# Virulent_HW.net
KiCad netlist of a schematic drawn in EAGLE
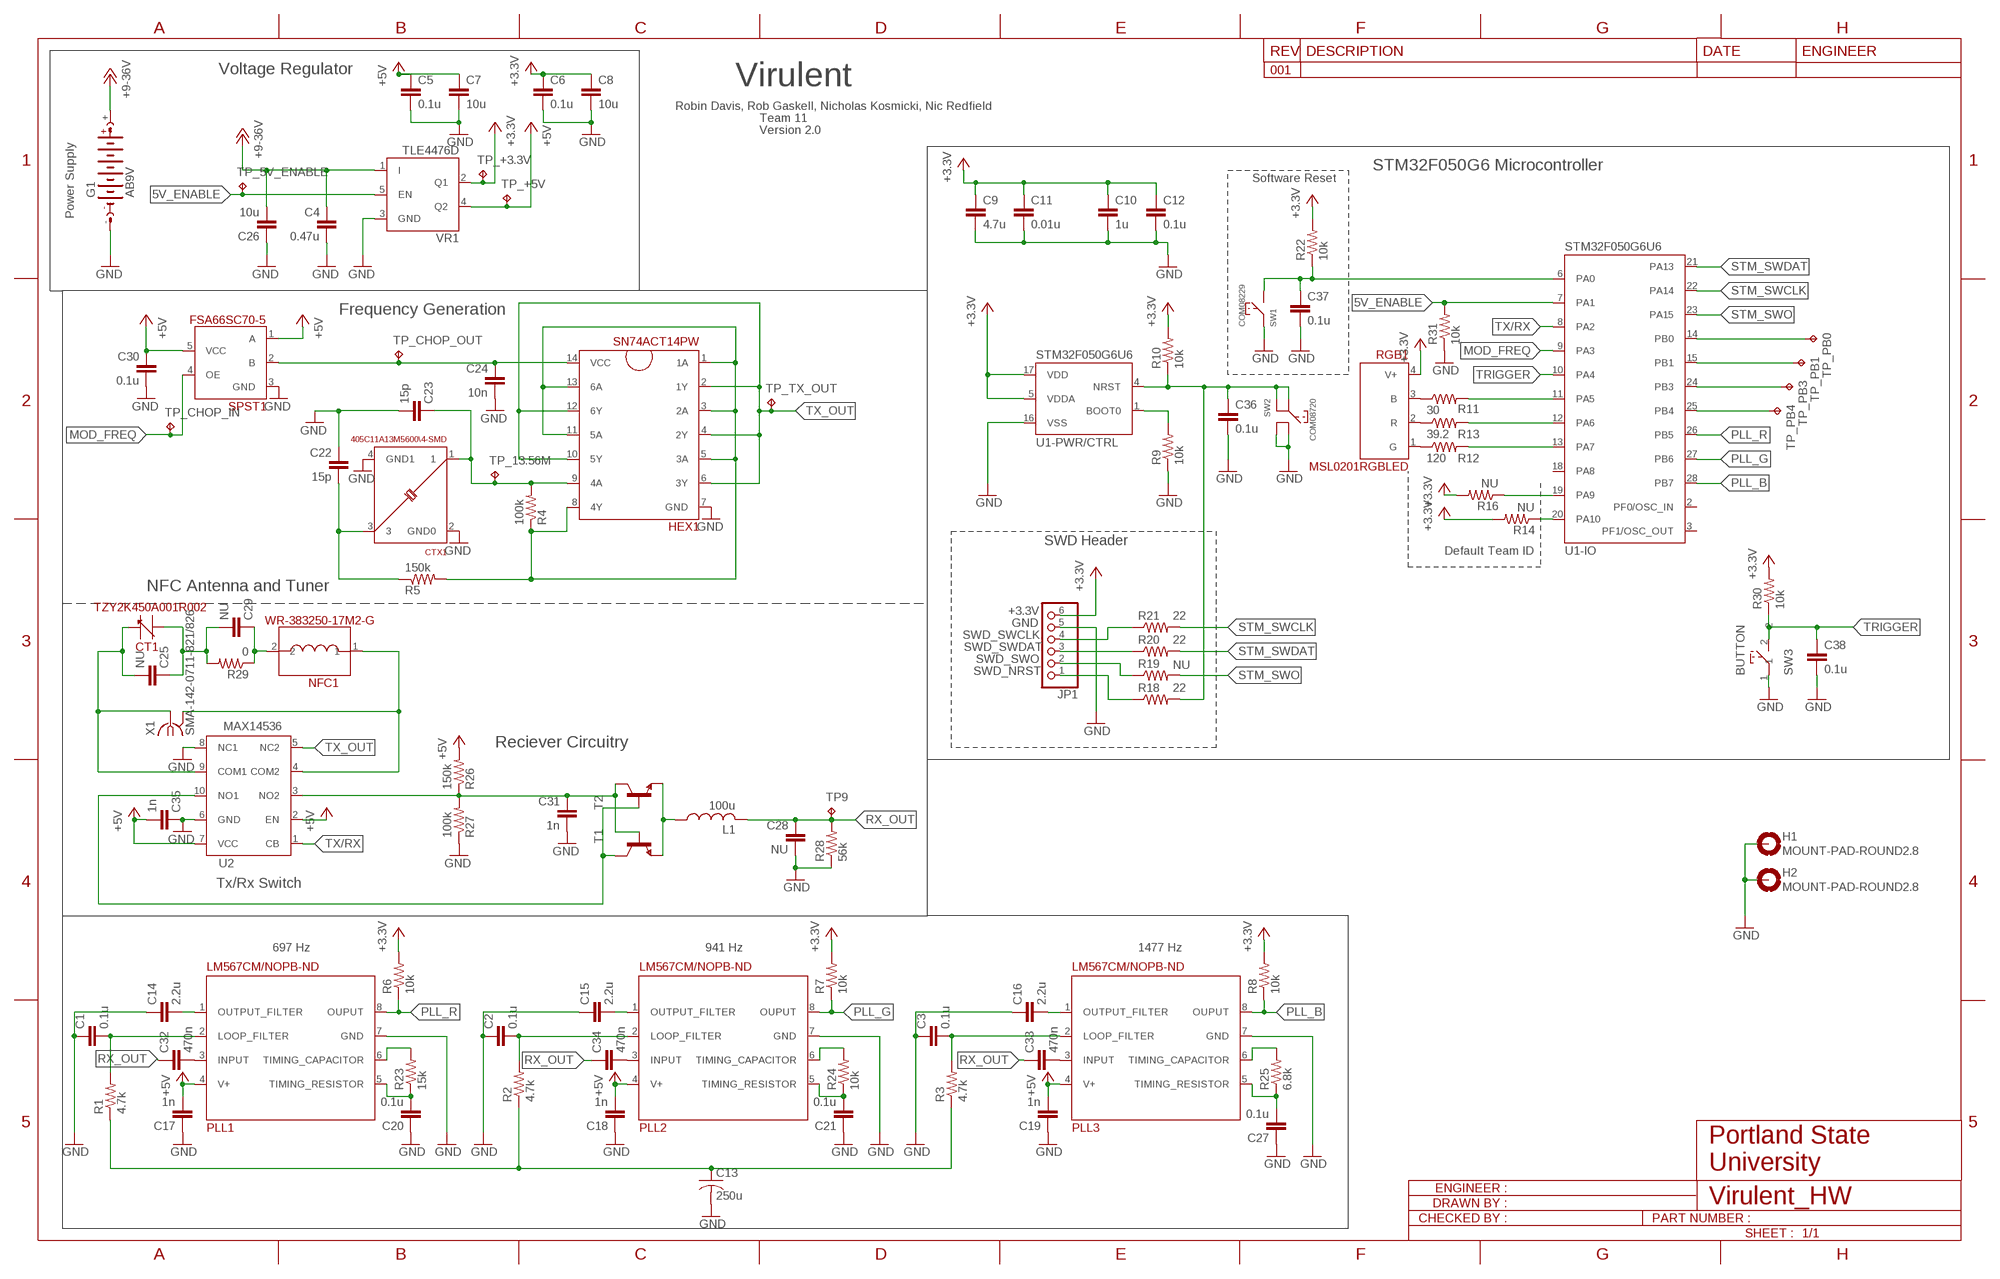
[diagram p0: schematic, sheet 1]

(export (version "E")
  (design (tool "Eeschema 10.0.6"))
  (components
    (comp (ref "C1")
      (value "0.1u")
      (footprint "eagle-import:C0402")
      (libsource (lib "eagle-import") (part "C-EUC0402"))
    )
    (comp (ref "C2")
      (value "0.1u")
      (footprint "eagle-import:C0402")
      (libsource (lib "eagle-import") (part "C-EUC0402"))
    )
    (comp (ref "C3")
      (value "0.1u")
      (footprint "eagle-import:C0402")
      (libsource (lib "eagle-import") (part "C-EUC0402"))
    )
    (comp (ref "C4")
      (value "0.47u")
      (footprint "eagle-import:C1206")
      (libsource (lib "eagle-import") (part "C-EUC1206"))
    )
    (comp (ref "C5")
      (value "0.1u")
      (footprint "eagle-import:C0402")
      (libsource (lib "eagle-import") (part "C-EUC0402"))
    )
    (comp (ref "C6")
      (value "0.1u")
      (footprint "eagle-import:C0402")
      (libsource (lib "eagle-import") (part "C-EUC0402"))
    )
    (comp (ref "C7")
      (value "10u")
      (footprint "eagle-import:C1206")
      (libsource (lib "eagle-import") (part "C-EUC1206"))
    )
    (comp (ref "C8")
      (value "10u")
      (footprint "eagle-import:C1206")
      (libsource (lib "eagle-import") (part "C-EUC1206"))
    )
    (comp (ref "C9")
      (value "4.7u")
      (footprint "eagle-import:C0805")
      (libsource (lib "eagle-import") (part "C-EUC0805"))
    )
    (comp (ref "C10")
      (value "1u")
      (footprint "eagle-import:C0805")
      (libsource (lib "eagle-import") (part "C-EUC0805"))
    )
    (comp (ref "C11")
      (value "0.01u")
      (footprint "eagle-import:C0402")
      (libsource (lib "eagle-import") (part "C-EUC0402"))
    )
    (comp (ref "C12")
      (value "0.1u")
      (footprint "eagle-import:C0402")
      (libsource (lib "eagle-import") (part "C-EUC0402"))
    )
    (comp (ref "C13")
      (value "250u")
      (footprint "eagle-import:C1210")
      (libsource (lib "eagle-import") (part "C-USC1210"))
    )
    (comp (ref "C14")
      (value "2.2u")
      (footprint "eagle-import:C0402")
      (libsource (lib "eagle-import") (part "C-EUC0402"))
    )
    (comp (ref "C15")
      (value "2.2u")
      (footprint "eagle-import:C0402")
      (libsource (lib "eagle-import") (part "C-EUC0402"))
    )
    (comp (ref "C16")
      (value "2.2u")
      (footprint "eagle-import:C0402")
      (libsource (lib "eagle-import") (part "C-EUC0402"))
    )
    (comp (ref "C17")
      (value "1n")
      (footprint "eagle-import:C0402")
      (libsource (lib "eagle-import") (part "C-EUC0402"))
    )
    (comp (ref "C18")
      (value "1n")
      (footprint "eagle-import:C0402")
      (libsource (lib "eagle-import") (part "C-EUC0402"))
    )
    (comp (ref "C19")
      (value "1n")
      (footprint "eagle-import:C0402")
      (libsource (lib "eagle-import") (part "C-EUC0402"))
    )
    (comp (ref "C20")
      (value "0.1u")
      (footprint "eagle-import:C0402")
      (libsource (lib "eagle-import") (part "C-EUC0402"))
    )
    (comp (ref "C21")
      (value "0.1u")
      (footprint "eagle-import:C0402")
      (libsource (lib "eagle-import") (part "C-EUC0402"))
    )
    (comp (ref "C22")
      (value "15p")
      (footprint "eagle-import:C0402")
      (libsource (lib "eagle-import") (part "C-EUC0402"))
    )
    (comp (ref "C23")
      (value "15p")
      (footprint "eagle-import:C0402")
      (libsource (lib "eagle-import") (part "C-EUC0402"))
    )
    (comp (ref "C24")
      (value "10n")
      (footprint "eagle-import:C0402")
      (libsource (lib "eagle-import") (part "C-EUC0402"))
    )
    (comp (ref "C25")
      (value "NU")
      (footprint "eagle-import:C0402")
      (libsource (lib "eagle-import") (part "C-EUC0402"))
    )
    (comp (ref "C26")
      (value "10u")
      (footprint "eagle-import:C1206")
      (libsource (lib "eagle-import") (part "C-EUC1206"))
    )
    (comp (ref "C27")
      (value "0.1u")
      (footprint "eagle-import:C0402")
      (libsource (lib "eagle-import") (part "C-EUC0402"))
    )
    (comp (ref "C28")
      (value "NU")
      (footprint "eagle-import:C0402")
      (libsource (lib "eagle-import") (part "C-EUC0402"))
    )
    (comp (ref "C29")
      (value "NU")
      (footprint "eagle-import:C0402")
      (libsource (lib "eagle-import") (part "C-EUC0402"))
    )
    (comp (ref "C30")
      (value "0.1u")
      (footprint "eagle-import:C0402")
      (libsource (lib "eagle-import") (part "C-EUC0402"))
    )
    (comp (ref "C31")
      (value "1n")
      (footprint "eagle-import:C0402")
      (libsource (lib "eagle-import") (part "C-EUC0402"))
    )
    (comp (ref "C32")
      (value "470n")
      (footprint "eagle-import:C0402")
      (libsource (lib "eagle-import") (part "C-EUC0402"))
    )
    (comp (ref "C33")
      (value "470n")
      (footprint "eagle-import:C0402")
      (libsource (lib "eagle-import") (part "C-EUC0402"))
    )
    (comp (ref "C34")
      (value "470n")
      (footprint "eagle-import:C0402")
      (libsource (lib "eagle-import") (part "C-EUC0402"))
    )
    (comp (ref "C35")
      (value "1n")
      (footprint "eagle-import:C0402")
      (libsource (lib "eagle-import") (part "C-EUC0402"))
    )
    (comp (ref "C36")
      (value "0.1u")
      (footprint "eagle-import:C0603")
      (libsource (lib "eagle-import") (part "C-EUC0603"))
    )
    (comp (ref "C37")
      (value "0.1u")
      (footprint "eagle-import:C0603")
      (libsource (lib "eagle-import") (part "C-EUC0603"))
    )
    (comp (ref "C38")
      (value "0.1u")
      (footprint "eagle-import:C0603")
      (libsource (lib "eagle-import") (part "C-EUC0603"))
    )
    (comp (ref "CT1")
      (value "TZY2K450A001R002")
      (footprint "eagle-import:TZY2")
      (libsource (lib "eagle-import") (part "TZY2K450A001R002"))
    )
    (comp (ref "CTX1")
      (value "405C11A13M5600\\4-SMD")
      (footprint "eagle-import:4-SMD")
      (libsource (lib "eagle-import") (part "405C11A13M5600{backslash}4-SMD"))
    )
    (comp (ref "G1")
      (value "AB9V")
      (footprint "eagle-import:AB9V")
      (libsource (lib "eagle-import") (part "AB9V"))
    )
    (comp (ref "H1")
      (value "MOUNT-PAD-ROUND2.8")
      (footprint "eagle-import:2,8-PAD")
      (libsource (lib "eagle-import") (part "MOUNT-PAD-ROUND2.8"))
    )
    (comp (ref "H2")
      (value "MOUNT-PAD-ROUND2.8")
      (footprint "eagle-import:2,8-PAD")
      (libsource (lib "eagle-import") (part "MOUNT-PAD-ROUND2.8"))
    )
    (comp (ref "HEX1")
      (value "SN74ACT14PW")
      (footprint "eagle-import:TSSOP14")
      (libsource (lib "eagle-import") (part "SN74ACT14PW"))
    )
    (comp (ref "JP1")
      (value "PINHD-1X6")
      (footprint "eagle-import:1X06")
      (libsource (lib "eagle-import") (part "PINHD-1X6"))
    )
    (comp (ref "L1")
      (value "100u")
      (footprint "eagle-import:L1008")
      (libsource (lib "eagle-import") (part "L-USL1008"))
    )
    (comp (ref "NFC1")
      (value "WR-383250-17M2-G")
      (footprint "eagle-import:17M2-G")
      (libsource (lib "eagle-import") (part "WR-383250-17M2-G"))
    )
    (comp (ref "PLL1")
      (value "LM567CM/NOPB-ND")
      (footprint "eagle-import:SOIC-8")
      (libsource (lib "eagle-import") (part "LM567CM/NOPB-ND"))
    )
    (comp (ref "PLL2")
      (value "LM567CM/NOPB-ND")
      (footprint "eagle-import:SOIC-8")
      (libsource (lib "eagle-import") (part "LM567CM/NOPB-ND"))
    )
    (comp (ref "PLL3")
      (value "LM567CM/NOPB-ND")
      (footprint "eagle-import:SOIC-8")
      (libsource (lib "eagle-import") (part "LM567CM/NOPB-ND"))
    )
    (comp (ref "R1")
      (value "4.7k")
      (footprint "eagle-import:R0402")
      (libsource (lib "eagle-import") (part "R-US_R0402"))
    )
    (comp (ref "R2")
      (value "4.7k")
      (footprint "eagle-import:R0402")
      (libsource (lib "eagle-import") (part "R-US_R0402"))
    )
    (comp (ref "R3")
      (value "4.7k")
      (footprint "eagle-import:R0402")
      (libsource (lib "eagle-import") (part "R-US_R0402"))
    )
    (comp (ref "R4")
      (value "100k")
      (footprint "eagle-import:R0402")
      (libsource (lib "eagle-import") (part "R-US_R0402"))
    )
    (comp (ref "R5")
      (value "150k")
      (footprint "eagle-import:R0402")
      (libsource (lib "eagle-import") (part "R-US_R0402"))
    )
    (comp (ref "R6")
      (value "10k")
      (footprint "eagle-import:R0402")
      (libsource (lib "eagle-import") (part "R-US_R0402"))
    )
    (comp (ref "R7")
      (value "10k")
      (footprint "eagle-import:R0402")
      (libsource (lib "eagle-import") (part "R-US_R0402"))
    )
    (comp (ref "R8")
      (value "10k")
      (footprint "eagle-import:R0402")
      (libsource (lib "eagle-import") (part "R-US_R0402"))
    )
    (comp (ref "R9")
      (value "10k")
      (footprint "eagle-import:R0402")
      (libsource (lib "eagle-import") (part "R-US_R0402"))
    )
    (comp (ref "R10")
      (value "10k")
      (footprint "eagle-import:R0402")
      (libsource (lib "eagle-import") (part "R-US_R0402"))
    )
    (comp (ref "R11")
      (value "30")
      (footprint "eagle-import:R0402")
      (libsource (lib "eagle-import") (part "R-US_R0402"))
    )
    (comp (ref "R12")
      (value "120")
      (footprint "eagle-import:R0402")
      (libsource (lib "eagle-import") (part "R-US_R0402"))
    )
    (comp (ref "R13")
      (value "39.2")
      (footprint "eagle-import:R0402")
      (libsource (lib "eagle-import") (part "R-US_R0402"))
    )
    (comp (ref "R14")
      (value "NU")
      (footprint "eagle-import:R0402")
      (libsource (lib "eagle-import") (part "R-US_R0402"))
    )
    (comp (ref "R16")
      (value "NU")
      (footprint "eagle-import:R0402")
      (libsource (lib "eagle-import") (part "R-US_R0402"))
    )
    (comp (ref "R18")
      (value "22")
      (footprint "eagle-import:R0402")
      (libsource (lib "eagle-import") (part "R-US_R0402"))
    )
    (comp (ref "R19")
      (value "NU")
      (footprint "eagle-import:R0402")
      (libsource (lib "eagle-import") (part "R-US_R0402"))
    )
    (comp (ref "R20")
      (value "22")
      (footprint "eagle-import:R0402")
      (libsource (lib "eagle-import") (part "R-US_R0402"))
    )
    (comp (ref "R21")
      (value "22")
      (footprint "eagle-import:R0402")
      (libsource (lib "eagle-import") (part "R-US_R0402"))
    )
    (comp (ref "R22")
      (value "10k")
      (footprint "eagle-import:R0402")
      (libsource (lib "eagle-import") (part "R-US_R0402"))
    )
    (comp (ref "R23")
      (value "15k")
      (footprint "eagle-import:R0402")
      (libsource (lib "eagle-import") (part "R-US_R0402"))
    )
    (comp (ref "R24")
      (value "10k")
      (footprint "eagle-import:R0402")
      (libsource (lib "eagle-import") (part "R-US_R0402"))
    )
    (comp (ref "R25")
      (value "6.8k")
      (footprint "eagle-import:R0402")
      (libsource (lib "eagle-import") (part "R-US_R0402"))
    )
    (comp (ref "R26")
      (value "150k")
      (footprint "eagle-import:R0402")
      (libsource (lib "eagle-import") (part "R-US_R0402"))
    )
    (comp (ref "R27")
      (value "100k")
      (footprint "eagle-import:R0402")
      (libsource (lib "eagle-import") (part "R-US_R0402"))
    )
    (comp (ref "R28")
      (value "56k")
      (footprint "eagle-import:R0402")
      (libsource (lib "eagle-import") (part "R-US_R0402"))
    )
    (comp (ref "R29")
      (value "0")
      (footprint "eagle-import:R0402")
      (libsource (lib "eagle-import") (part "R-US_R0402"))
    )
    (comp (ref "R30")
      (value "10k")
      (footprint "eagle-import:R0402")
      (libsource (lib "eagle-import") (part "R-US_R0402"))
    )
    (comp (ref "R31")
      (value "10k")
      (footprint "eagle-import:R0402")
      (libsource (lib "eagle-import") (part "R-US_R0402"))
    )
    (comp (ref "RGB1")
      (value "MSL0201RGBLED")
      (footprint "eagle-import:MSL0201RGB")
      (libsource (lib "eagle-import") (part "MSL0201RGBLED"))
    )
    (comp (ref "SPST1")
      (value "FSA66SC70-5")
      (footprint "eagle-import:6-TSSOP")
      (libsource (lib "eagle-import") (part "FSA66SC70-5"))
    )
    (comp (ref "SW1")
      (value "COM08229")
      (footprint "eagle-import:COM08229")
      (libsource (lib "eagle-import") (part "COM08229"))
    )
    (comp (ref "SW2")
      (value "COM08720")
      (footprint "eagle-import:COM08720")
      (libsource (lib "eagle-import") (part "COM08720"))
    )
    (comp (ref "SW3")
      (value "BUTTON")
      (footprint "eagle-import:17M2-G")
      (libsource (lib "eagle-import") (part "BUTTON"))
    )
    (comp (ref "T1")
      (value "2N2222-NPN-TO18-EBC")
      (footprint "eagle-import:TO18")
      (libsource (lib "eagle-import") (part "-NPN-TO18-EBC2N2222"))
    )
    (comp (ref "T2")
      (value "2N2222-NPN-TO18-EBC")
      (footprint "eagle-import:TO18")
      (libsource (lib "eagle-import") (part "-NPN-TO18-EBC2N2222"))
    )
    (comp (ref "TP9")
      (value "TPTP06SQ")
      (footprint "eagle-import:TP06SQ")
      (libsource (lib "eagle-import") (part "TPTP06SQ"))
    )
    (comp (ref "TP_+3.3V")
      (value "TPTP06SQ")
      (footprint "eagle-import:TP06SQ")
      (libsource (lib "eagle-import") (part "TPTP06SQ"))
    )
    (comp (ref "TP_+5V")
      (value "TPTP06SQ")
      (footprint "eagle-import:TP06SQ")
      (libsource (lib "eagle-import") (part "TPTP06SQ"))
    )
    (comp (ref "TP_5V_ENABLE")
      (value "TPTP06SQ")
      (footprint "eagle-import:TP06SQ")
      (libsource (lib "eagle-import") (part "TPTP06SQ"))
    )
    (comp (ref "TP_13.56M")
      (value "TPTP06SQ")
      (footprint "eagle-import:TP06SQ")
      (libsource (lib "eagle-import") (part "TPTP06SQ"))
    )
    (comp (ref "TP_CHOP_IN")
      (value "TPTP06SQ")
      (footprint "eagle-import:TP06SQ")
      (libsource (lib "eagle-import") (part "TPTP06SQ"))
    )
    (comp (ref "TP_CHOP_OUT")
      (value "TPTP06SQ")
      (footprint "eagle-import:TP06SQ")
      (libsource (lib "eagle-import") (part "TPTP06SQ"))
    )
    (comp (ref "TP_PB0")
      (value "TPTP06SQ")
      (footprint "eagle-import:TP06SQ")
      (libsource (lib "eagle-import") (part "TPTP06SQ"))
    )
    (comp (ref "TP_PB1")
      (value "TPTP06SQ")
      (footprint "eagle-import:TP06SQ")
      (libsource (lib "eagle-import") (part "TPTP06SQ"))
    )
    (comp (ref "TP_PB3")
      (value "TPTP06SQ")
      (footprint "eagle-import:TP06SQ")
      (libsource (lib "eagle-import") (part "TPTP06SQ"))
    )
    (comp (ref "TP_PB4")
      (value "TPTP06SQ")
      (footprint "eagle-import:TP06SQ")
      (libsource (lib "eagle-import") (part "TPTP06SQ"))
    )
    (comp (ref "TP_TX_OUT")
      (value "TPTP06SQ")
      (footprint "eagle-import:TP06SQ")
      (libsource (lib "eagle-import") (part "TPTP06SQ"))
    )
    (comp (ref "U1")
      (value "STM32F050G6U6")
      (footprint "eagle-import:UQFPN-28")
      (libsource (lib "eagle-import") (part "STM32F050G6U6"))
    )
    (comp (ref "U2")
      (value "MAX14536")
      (footprint "eagle-import:10UTQFN")
      (libsource (lib "eagle-import") (part "MAX14536"))
    )
    (comp (ref "VR1")
      (value "TLE4476D")
      (footprint "eagle-import:PG-TO252-5-11")
      (libsource (lib "eagle-import") (part "TLE4476D"))
    )
    (comp (ref "X1")
      (value "SMA-142-0711-821/826")
      (footprint "eagle-import:J502-ND-142-0711-821_826")
      (fields (field (name "MF") "JOHNSON COMPONENTS") (field (name "MPN") "142-0711-821"))
      (libsource (lib "eagle-import") (part "SMA-142-0711-821/826"))
    )
  )
  (nets
    (net (code "1") (name "+3.3V") (class "Default")
      (node (ref "C10") (pin "1") (pinfunction "1_1") (pintype "passive"))
      (node (ref "C11") (pin "1") (pinfunction "1_1") (pintype "passive"))
      (node (ref "C12") (pin "1") (pinfunction "1_1") (pintype "passive"))
      (node (ref "C6") (pin "1") (pinfunction "1_1") (pintype "passive"))
      (node (ref "C8") (pin "1") (pinfunction "1_1") (pintype "passive"))
      (node (ref "C9") (pin "1") (pinfunction "1_1") (pintype "passive"))
      (node (ref "JP1") (pin "6") (pinfunction "6_6") (pintype "passive"))
      (node (ref "R10") (pin "2") (pinfunction "2_2") (pintype "passive"))
      (node (ref "R14") (pin "2") (pinfunction "2_2") (pintype "passive"))
      (node (ref "R16") (pin "2") (pinfunction "2_2") (pintype "passive"))
      (node (ref "R22") (pin "2") (pinfunction "2_2") (pintype "passive"))
      (node (ref "R30") (pin "2") (pinfunction "2_2") (pintype "passive"))
      (node (ref "R6") (pin "2") (pinfunction "2_2") (pintype "passive"))
      (node (ref "R7") (pin "2") (pinfunction "2_2") (pintype "passive"))
      (node (ref "R8") (pin "2") (pinfunction "2_2") (pintype "passive"))
      (node (ref "RGB1") (pin "4") (pinfunction "V+_4") (pintype "power_in"))
      (node (ref "TP_+3.3V") (pin "TP") (pinfunction "TP_TP") (pintype "input"))
      (node (ref "U1") (pin "17") (pinfunction "VDD_17") (pintype "power_in"))
      (node (ref "U1") (pin "5") (pinfunction "VDDA_5") (pintype "power_in"))
      (node (ref "VR1") (pin "2") (pinfunction "Q1_2") (pintype "bidirectional"))
    )
    (net (code "2") (name "+5V") (class "Default")
      (node (ref "C17") (pin "2") (pinfunction "2_2") (pintype "passive"))
      (node (ref "C18") (pin "2") (pinfunction "2_2") (pintype "passive"))
      (node (ref "C19") (pin "2") (pinfunction "2_2") (pintype "passive"))
      (node (ref "C30") (pin "1") (pinfunction "1_1") (pintype "passive"))
      (node (ref "C35") (pin "2") (pinfunction "2_2") (pintype "passive"))
      (node (ref "C5") (pin "1") (pinfunction "1_1") (pintype "passive"))
      (node (ref "C7") (pin "1") (pinfunction "1_1") (pintype "passive"))
      (node (ref "PLL1") (pin "4") (pinfunction "V+_4") (pintype "bidirectional"))
      (node (ref "PLL2") (pin "4") (pinfunction "V+_4") (pintype "bidirectional"))
      (node (ref "PLL3") (pin "4") (pinfunction "V+_4") (pintype "bidirectional"))
      (node (ref "R26") (pin "2") (pinfunction "2_2") (pintype "passive"))
      (node (ref "SPST1") (pin "1") (pinfunction "A_1") (pintype "bidirectional"))
      (node (ref "SPST1") (pin "5") (pinfunction "VCC_5") (pintype "power_in"))
      (node (ref "TP_+5V") (pin "TP") (pinfunction "TP_TP") (pintype "input"))
      (node (ref "U2") (pin "2") (pinfunction "EN_2") (pintype "bidirectional"))
      (node (ref "U2") (pin "7") (pinfunction "VCC_7") (pintype "bidirectional"))
      (node (ref "VR1") (pin "4") (pinfunction "Q2_4") (pintype "bidirectional"))
    )
    (net (code "3") (name "+9-36V") (class "Default")
      (node (ref "C26") (pin "2") (pinfunction "2_2") (pintype "passive"))
      (node (ref "C4") (pin "1") (pinfunction "1_1") (pintype "passive"))
      (node (ref "G1") (pin "+") (pinfunction "+_+") (pintype "passive"))
      (node (ref "VR1") (pin "1") (pinfunction "I_1") (pintype "bidirectional"))
    )
    (net (code "4") (name "/SWD_NRST") (class "Default")
      (node (ref "JP1") (pin "1") (pinfunction "1_1") (pintype "passive"))
      (node (ref "R18") (pin "1") (pinfunction "1_1") (pintype "passive"))
    )
    (net (code "5") (name "/SWD_SWCLK") (class "Default")
      (node (ref "JP1") (pin "4") (pinfunction "4_4") (pintype "passive"))
      (node (ref "R21") (pin "1") (pinfunction "1_1") (pintype "passive"))
    )
    (net (code "6") (name "/SWD_SWDAT") (class "Default")
      (node (ref "JP1") (pin "3") (pinfunction "3_3") (pintype "passive"))
      (node (ref "R20") (pin "1") (pinfunction "1_1") (pintype "passive"))
    )
    (net (code "7") (name "/SWD_SWO") (class "Default")
      (node (ref "JP1") (pin "2") (pinfunction "2_2") (pintype "passive"))
      (node (ref "R19") (pin "1") (pinfunction "1_1") (pintype "passive"))
    )
    (net (code "8") (name "5V_ENABLE") (class "Default")
      (node (ref "R31") (pin "2") (pinfunction "2_2") (pintype "passive"))
      (node (ref "TP_5V_ENABLE") (pin "TP") (pinfunction "TP_TP") (pintype "input"))
      (node (ref "U1") (pin "7") (pinfunction "PA1_7") (pintype "bidirectional"))
      (node (ref "VR1") (pin "5") (pinfunction "EN_5") (pintype "bidirectional"))
    )
    (net (code "9") (name "GND") (class "Default")
      (node (ref "C1") (pin "1") (pinfunction "1_1") (pintype "passive"))
      (node (ref "C10") (pin "2") (pinfunction "2_2") (pintype "passive"))
      (node (ref "C11") (pin "2") (pinfunction "2_2") (pintype "passive"))
      (node (ref "C12") (pin "2") (pinfunction "2_2") (pintype "passive"))
      (node (ref "C13") (pin "2") (pinfunction "2_2") (pintype "passive"))
      (node (ref "C14") (pin "1") (pinfunction "1_1") (pintype "passive"))
      (node (ref "C15") (pin "1") (pinfunction "1_1") (pintype "passive"))
      (node (ref "C16") (pin "1") (pinfunction "1_1") (pintype "passive"))
      (node (ref "C17") (pin "1") (pinfunction "1_1") (pintype "passive"))
      (node (ref "C18") (pin "1") (pinfunction "1_1") (pintype "passive"))
      (node (ref "C19") (pin "1") (pinfunction "1_1") (pintype "passive"))
      (node (ref "C2") (pin "1") (pinfunction "1_1") (pintype "passive"))
      (node (ref "C20") (pin "1") (pinfunction "1_1") (pintype "passive"))
      (node (ref "C21") (pin "1") (pinfunction "1_1") (pintype "passive"))
      (node (ref "C22") (pin "1") (pinfunction "1_1") (pintype "passive"))
      (node (ref "C23") (pin "2") (pinfunction "2_2") (pintype "passive"))
      (node (ref "C24") (pin "2") (pinfunction "2_2") (pintype "passive"))
      (node (ref "C26") (pin "1") (pinfunction "1_1") (pintype "passive"))
      (node (ref "C27") (pin "1") (pinfunction "1_1") (pintype "passive"))
      (node (ref "C28") (pin "2") (pinfunction "2_2") (pintype "passive"))
      (node (ref "C3") (pin "1") (pinfunction "1_1") (pintype "passive"))
      (node (ref "C30") (pin "2") (pinfunction "2_2") (pintype "passive"))
      (node (ref "C31") (pin "2") (pinfunction "2_2") (pintype "passive"))
      (node (ref "C35") (pin "1") (pinfunction "1_1") (pintype "passive"))
      (node (ref "C36") (pin "2") (pinfunction "2_2") (pintype "passive"))
      (node (ref "C37") (pin "2") (pinfunction "2_2") (pintype "passive"))
      (node (ref "C38") (pin "2") (pinfunction "2_2") (pintype "passive"))
      (node (ref "C4") (pin "2") (pinfunction "2_2") (pintype "passive"))
      (node (ref "C5") (pin "2") (pinfunction "2_2") (pintype "passive"))
      (node (ref "C6") (pin "2") (pinfunction "2_2") (pintype "passive"))
      (node (ref "C7") (pin "2") (pinfunction "2_2") (pintype "passive"))
      (node (ref "C8") (pin "2") (pinfunction "2_2") (pintype "passive"))
      (node (ref "C9") (pin "2") (pinfunction "2_2") (pintype "passive"))
      (node (ref "CTX1") (pin "2") (pinfunction "GND0_2") (pintype "power_in"))
      (node (ref "CTX1") (pin "4") (pinfunction "GND1_4") (pintype "power_in"))
      (node (ref "G1") (pin "-") (pinfunction "-_-") (pintype "passive"))
      (node (ref "H1") (pin "B2,8") (pinfunction "MOUNT_B2,8") (pintype "passive"))
      (node (ref "H2") (pin "B2,8") (pinfunction "MOUNT_B2,8") (pintype "passive"))
      (node (ref "HEX1") (pin "7") (pinfunction "GND_7") (pintype "power_in"))
      (node (ref "JP1") (pin "5") (pinfunction "5_5") (pintype "passive"))
      (node (ref "PLL1") (pin "7") (pinfunction "GND_7") (pintype "bidirectional"))
      (node (ref "PLL2") (pin "7") (pinfunction "GND_7") (pintype "bidirectional"))
      (node (ref "PLL3") (pin "7") (pinfunction "GND_7") (pintype "bidirectional"))
      (node (ref "R27") (pin "1") (pinfunction "1_1") (pintype "passive"))
      (node (ref "R28") (pin "1") (pinfunction "1_1") (pintype "passive"))
      (node (ref "R31") (pin "1") (pinfunction "1_1") (pintype "passive"))
      (node (ref "R9") (pin "1") (pinfunction "1_1") (pintype "passive"))
      (node (ref "SPST1") (pin "3") (pinfunction "GND_3") (pintype "power_in"))
      (node (ref "SW1") (pin "1") (pinfunction "1_1") (pintype "bidirectional"))
      (node (ref "SW2") (pin "3") (pinfunction "3_3") (pintype "bidirectional"))
      (node (ref "SW2") (pin "4") (pinfunction "4_4") (pintype "bidirectional"))
      (node (ref "SW3") (pin "1") (pinfunction "1_1") (pintype "bidirectional"))
      (node (ref "U1") (pin "16") (pinfunction "VSS_16") (pintype "power_in"))
      (node (ref "U2") (pin "6") (pinfunction "GND_6") (pintype "bidirectional"))
      (node (ref "U2") (pin "8") (pinfunction "NC1_8") (pintype "bidirectional"))
      (node (ref "VR1") (pin "3") (pinfunction "GND_3") (pintype "bidirectional"))
    )
    (net (code "10") (name "MOD_FREQ") (class "Default")
      (node (ref "SPST1") (pin "4") (pinfunction "OE_4") (pintype "bidirectional"))
      (node (ref "TP_CHOP_IN") (pin "TP") (pinfunction "TP_TP") (pintype "input"))
      (node (ref "U1") (pin "9") (pinfunction "PA3_9") (pintype "bidirectional"))
    )
    (net (code "11") (name "Net-(C13-Pad1)") (class "Default")
      (node (ref "C13") (pin "1") (pinfunction "1_1") (pintype "passive"))
      (node (ref "R1") (pin "1") (pinfunction "1_1") (pintype "passive"))
      (node (ref "R2") (pin "1") (pinfunction "1_1") (pintype "passive"))
      (node (ref "R3") (pin "1") (pinfunction "1_1") (pintype "passive"))
    )
    (net (code "12") (name "Net-(C22-Pad2)") (class "Default")
      (node (ref "C22") (pin "2") (pinfunction "2_2") (pintype "passive"))
      (node (ref "CTX1") (pin "3") (pinfunction "3_3") (pintype "bidirectional"))
      (node (ref "R5") (pin "1") (pinfunction "1_1") (pintype "passive"))
    )
    (net (code "13") (name "Net-(C29-Pad1)") (class "Default")
      (node (ref "C29") (pin "1") (pinfunction "1_1") (pintype "passive"))
      (node (ref "NFC1") (pin "2") (pinfunction "2_2") (pintype "power_in"))
      (node (ref "R29") (pin "1") (pinfunction "1_1") (pintype "passive"))
    )
    (net (code "14") (name "Net-(CT1-A)") (class "Default")
      (node (ref "C25") (pin "1") (pinfunction "1_1") (pintype "passive"))
      (node (ref "C29") (pin "2") (pinfunction "2_2") (pintype "passive"))
      (node (ref "CT1") (pin "1") (pinfunction "A_1") (pintype "power_in"))
      (node (ref "R29") (pin "2") (pinfunction "2_2") (pintype "passive"))
    )
    (net (code "15") (name "Net-(CT1-B)") (class "Default")
      (node (ref "C25") (pin "2") (pinfunction "2_2") (pintype "passive"))
      (node (ref "CT1") (pin "2") (pinfunction "B_2") (pintype "power_in"))
      (node (ref "U2") (pin "9") (pinfunction "COM1_9") (pintype "bidirectional"))
      (node (ref "X1") (pin "1") (pinfunction "1_1") (pintype "passive"))
    )
    (net (code "16") (name "Net-(HEX1-1A)") (class "Default")
      (node (ref "HEX1") (pin "1") (pinfunction "1A_1") (pintype "bidirectional"))
      (node (ref "HEX1") (pin "11") (pinfunction "5A_11") (pintype "bidirectional"))
      (node (ref "HEX1") (pin "13") (pinfunction "6A_13") (pintype "bidirectional"))
      (node (ref "HEX1") (pin "3") (pinfunction "2A_3") (pintype "bidirectional"))
      (node (ref "HEX1") (pin "5") (pinfunction "3A_5") (pintype "bidirectional"))
      (node (ref "HEX1") (pin "8") (pinfunction "4Y_8") (pintype "bidirectional"))
      (node (ref "R4") (pin "1") (pinfunction "1_1") (pintype "passive"))
      (node (ref "R5") (pin "2") (pinfunction "2_2") (pintype "passive"))
    )
    (net (code "17") (name "Net-(HEX1-4A)") (class "Default")
      (node (ref "C23") (pin "1") (pinfunction "1_1") (pintype "passive"))
      (node (ref "CTX1") (pin "1") (pinfunction "1_1") (pintype "bidirectional"))
      (node (ref "HEX1") (pin "9") (pinfunction "4A_9") (pintype "bidirectional"))
      (node (ref "R4") (pin "2") (pinfunction "2_2") (pintype "passive"))
      (node (ref "TP_13.56M") (pin "TP") (pinfunction "TP_TP") (pintype "input"))
    )
    (net (code "18") (name "Net-(HEX1-VCC)") (class "Default")
      (node (ref "C24") (pin "1") (pinfunction "1_1") (pintype "passive"))
      (node (ref "HEX1") (pin "14") (pinfunction "VCC_14") (pintype "power_in"))
      (node (ref "SPST1") (pin "2") (pinfunction "B_2") (pintype "bidirectional"))
      (node (ref "TP_CHOP_OUT") (pin "TP") (pinfunction "TP_TP") (pintype "input"))
    )
    (net (code "19") (name "Net-(PLL1-INPUT)") (class "Default")
      (node (ref "C32") (pin "2") (pinfunction "2_2") (pintype "passive"))
      (node (ref "PLL1") (pin "3") (pinfunction "INPUT_3") (pintype "bidirectional"))
    )
    (net (code "20") (name "Net-(PLL1-LOOP_FILTER)") (class "Default")
      (node (ref "C1") (pin "2") (pinfunction "2_2") (pintype "passive"))
      (node (ref "PLL1") (pin "2") (pinfunction "LOOP_FILTER_2") (pintype "bidirectional"))
      (node (ref "R1") (pin "2") (pinfunction "2_2") (pintype "passive"))
    )
    (net (code "21") (name "Net-(PLL1-OUTPUT_FILTER)") (class "Default")
      (node (ref "C14") (pin "2") (pinfunction "2_2") (pintype "passive"))
      (node (ref "PLL1") (pin "1") (pinfunction "OUTPUT_FILTER_1") (pintype "bidirectional"))
    )
    (net (code "22") (name "Net-(PLL1-TIMING_CAPACITOR)") (class "Default")
      (node (ref "PLL1") (pin "6") (pinfunction "TIMING_CAPACITOR_6") (pintype "bidirectional"))
      (node (ref "R23") (pin "2") (pinfunction "2_2") (pintype "passive"))
    )
    (net (code "23") (name "Net-(PLL1-TIMING_RESISTOR)") (class "Default")
      (node (ref "C20") (pin "2") (pinfunction "2_2") (pintype "passive"))
      (node (ref "PLL1") (pin "5") (pinfunction "TIMING_RESISTOR_5") (pintype "bidirectional"))
      (node (ref "R23") (pin "1") (pinfunction "1_1") (pintype "passive"))
    )
    (net (code "24") (name "Net-(PLL2-INPUT)") (class "Default")
      (node (ref "C34") (pin "2") (pinfunction "2_2") (pintype "passive"))
      (node (ref "PLL2") (pin "3") (pinfunction "INPUT_3") (pintype "bidirectional"))
    )
    (net (code "25") (name "Net-(PLL2-LOOP_FILTER)") (class "Default")
      (node (ref "C2") (pin "2") (pinfunction "2_2") (pintype "passive"))
      (node (ref "PLL2") (pin "2") (pinfunction "LOOP_FILTER_2") (pintype "bidirectional"))
      (node (ref "R2") (pin "2") (pinfunction "2_2") (pintype "passive"))
    )
    (net (code "26") (name "Net-(PLL2-OUTPUT_FILTER)") (class "Default")
      (node (ref "C15") (pin "2") (pinfunction "2_2") (pintype "passive"))
      (node (ref "PLL2") (pin "1") (pinfunction "OUTPUT_FILTER_1") (pintype "bidirectional"))
    )
    (net (code "27") (name "Net-(PLL2-TIMING_CAPACITOR)") (class "Default")
      (node (ref "PLL2") (pin "6") (pinfunction "TIMING_CAPACITOR_6") (pintype "bidirectional"))
      (node (ref "R24") (pin "2") (pinfunction "2_2") (pintype "passive"))
    )
    (net (code "28") (name "Net-(PLL2-TIMING_RESISTOR)") (class "Default")
      (node (ref "C21") (pin "2") (pinfunction "2_2") (pintype "passive"))
      (node (ref "PLL2") (pin "5") (pinfunction "TIMING_RESISTOR_5") (pintype "bidirectional"))
      (node (ref "R24") (pin "1") (pinfunction "1_1") (pintype "passive"))
    )
    (net (code "29") (name "Net-(PLL3-INPUT)") (class "Default")
      (node (ref "C33") (pin "2") (pinfunction "2_2") (pintype "passive"))
      (node (ref "PLL3") (pin "3") (pinfunction "INPUT_3") (pintype "bidirectional"))
    )
    (net (code "30") (name "Net-(PLL3-LOOP_FILTER)") (class "Default")
      (node (ref "C3") (pin "2") (pinfunction "2_2") (pintype "passive"))
      (node (ref "PLL3") (pin "2") (pinfunction "LOOP_FILTER_2") (pintype "bidirectional"))
      (node (ref "R3") (pin "2") (pinfunction "2_2") (pintype "passive"))
    )
    (net (code "31") (name "Net-(PLL3-OUTPUT_FILTER)") (class "Default")
      (node (ref "C16") (pin "2") (pinfunction "2_2") (pintype "passive"))
      (node (ref "PLL3") (pin "1") (pinfunction "OUTPUT_FILTER_1") (pintype "bidirectional"))
    )
    (net (code "32") (name "Net-(PLL3-TIMING_CAPACITOR)") (class "Default")
      (node (ref "PLL3") (pin "6") (pinfunction "TIMING_CAPACITOR_6") (pintype "bidirectional"))
      (node (ref "R25") (pin "2") (pinfunction "2_2") (pintype "passive"))
    )
    (net (code "33") (name "Net-(PLL3-TIMING_RESISTOR)") (class "Default")
      (node (ref "C27") (pin "2") (pinfunction "2_2") (pintype "passive"))
      (node (ref "PLL3") (pin "5") (pinfunction "TIMING_RESISTOR_5") (pintype "bidirectional"))
      (node (ref "R25") (pin "1") (pinfunction "1_1") (pintype "passive"))
    )
    (net (code "34") (name "Net-(RGB1-B)") (class "Default")
      (node (ref "R11") (pin "1") (pinfunction "1_1") (pintype "passive"))
      (node (ref "RGB1") (pin "3") (pinfunction "B_3") (pintype "power_in"))
    )
    (net (code "35") (name "Net-(RGB1-G)") (class "Default")
      (node (ref "R12") (pin "1") (pinfunction "1_1") (pintype "passive"))
      (node (ref "RGB1") (pin "1") (pinfunction "G_1") (pintype "power_in"))
    )
    (net (code "36") (name "Net-(RGB1-R)") (class "Default")
      (node (ref "R13") (pin "1") (pinfunction "1_1") (pintype "passive"))
      (node (ref "RGB1") (pin "2") (pinfunction "R_2") (pintype "power_in"))
    )
    (net (code "37") (name "Net-(T1-B)") (class "Default")
      (node (ref "T1") (pin "2") (pinfunction "B_2") (pintype "passive"))
      (node (ref "T2") (pin "3") (pinfunction "C_3") (pintype "passive"))
      (node (ref "U2") (pin "10") (pinfunction "NO1_10") (pintype "bidirectional"))
    )
    (net (code "38") (name "Net-(T1-C)") (class "Default")
      (node (ref "C31") (pin "1") (pinfunction "1_1") (pintype "passive"))
      (node (ref "R26") (pin "1") (pinfunction "1_1") (pintype "passive"))
      (node (ref "R27") (pin "2") (pinfunction "2_2") (pintype "passive"))
      (node (ref "T1") (pin "3") (pinfunction "C_3") (pintype "passive"))
      (node (ref "T2") (pin "2") (pinfunction "B_2") (pintype "passive"))
      (node (ref "U2") (pin "3") (pinfunction "NO2_3") (pintype "bidirectional"))
    )
    (net (code "39") (name "Net-(T1-E)") (class "Default")
      (node (ref "L1") (pin "1") (pinfunction "1_1") (pintype "passive"))
      (node (ref "T1") (pin "1") (pinfunction "E_1") (pintype "passive"))
      (node (ref "T2") (pin "1") (pinfunction "E_1") (pintype "passive"))
    )
    (net (code "40") (name "Net-(U1A-PA0)") (class "Default")
      (node (ref "C37") (pin "1") (pinfunction "1_1") (pintype "passive"))
      (node (ref "R22") (pin "1") (pinfunction "1_1") (pintype "passive"))
      (node (ref "SW1") (pin "2") (pinfunction "2_2") (pintype "bidirectional"))
      (node (ref "U1") (pin "6") (pinfunction "PA0_6") (pintype "bidirectional"))
    )
    (net (code "41") (name "Net-(U1A-PA5)") (class "Default")
      (node (ref "R11") (pin "2") (pinfunction "2_2") (pintype "passive"))
      (node (ref "U1") (pin "11") (pinfunction "PA5_11") (pintype "bidirectional"))
    )
    (net (code "42") (name "Net-(U1A-PA6)") (class "Default")
      (node (ref "R13") (pin "2") (pinfunction "2_2") (pintype "passive"))
      (node (ref "U1") (pin "12") (pinfunction "PA6_12") (pintype "bidirectional"))
    )
    (net (code "43") (name "Net-(U1A-PA7)") (class "Default")
      (node (ref "R12") (pin "2") (pinfunction "2_2") (pintype "passive"))
      (node (ref "U1") (pin "13") (pinfunction "PA7_13") (pintype "bidirectional"))
    )
    (net (code "44") (name "Net-(U1A-PA9)") (class "Default")
      (node (ref "R16") (pin "1") (pinfunction "1_1") (pintype "passive"))
      (node (ref "U1") (pin "19") (pinfunction "PA9_19") (pintype "bidirectional"))
    )
    (net (code "45") (name "Net-(U1A-PA10)") (class "Default")
      (node (ref "R14") (pin "1") (pinfunction "1_1") (pintype "passive"))
      (node (ref "U1") (pin "20") (pinfunction "PA10_20") (pintype "bidirectional"))
    )
    (net (code "46") (name "Net-(U1A-PB0)") (class "Default")
      (node (ref "TP_PB0") (pin "TP") (pinfunction "TP_TP") (pintype "input"))
      (node (ref "U1") (pin "14") (pinfunction "PB0_14") (pintype "bidirectional"))
    )
    (net (code "47") (name "Net-(U1A-PB1)") (class "Default")
      (node (ref "TP_PB1") (pin "TP") (pinfunction "TP_TP") (pintype "input"))
      (node (ref "U1") (pin "15") (pinfunction "PB1_15") (pintype "bidirectional"))
    )
    (net (code "48") (name "Net-(U1A-PB3)") (class "Default")
      (node (ref "TP_PB3") (pin "TP") (pinfunction "TP_TP") (pintype "input"))
      (node (ref "U1") (pin "24") (pinfunction "PB3_24") (pintype "bidirectional"))
    )
    (net (code "49") (name "Net-(U1A-PB4)") (class "Default")
      (node (ref "TP_PB4") (pin "TP") (pinfunction "TP_TP") (pintype "input"))
      (node (ref "U1") (pin "25") (pinfunction "PB4_25") (pintype "bidirectional"))
    )
    (net (code "50") (name "Net-(U1B-BOOT0)") (class "Default")
      (node (ref "R9") (pin "2") (pinfunction "2_2") (pintype "passive"))
      (node (ref "U1") (pin "1") (pinfunction "BOOT0_1") (pintype "bidirectional"))
    )
    (net (code "51") (name "Net-(U1B-NRST)") (class "Default")
      (node (ref "C36") (pin "1") (pinfunction "1_1") (pintype "passive"))
      (node (ref "R10") (pin "1") (pinfunction "1_1") (pintype "passive"))
      (node (ref "R18") (pin "2") (pinfunction "2_2") (pintype "passive"))
      (node (ref "SW2") (pin "1") (pinfunction "1_1") (pintype "bidirectional"))
      (node (ref "SW2") (pin "2") (pinfunction "2_2") (pintype "bidirectional"))
      (node (ref "U1") (pin "4") (pinfunction "NRST_4") (pintype "bidirectional"))
    )
    (net (code "52") (name "Net-(U2-COM2)") (class "Default")
      (node (ref "NFC1") (pin "1") (pinfunction "1_1") (pintype "power_in"))
      (node (ref "U2") (pin "4") (pinfunction "COM2_4") (pintype "bidirectional"))
      (node (ref "X1") (pin "G@1") (pinfunction "2_G@1") (pintype "passive"))
      (node (ref "X1") (pin "G@2") (pinfunction "2_G@2") (pintype "passive"))
      (node (ref "X1") (pin "G@3") (pinfunction "2_G@3") (pintype "passive"))
      (node (ref "X1") (pin "G@4") (pinfunction "2_G@4") (pintype "passive"))
    )
    (net (code "53") (name "PLL_B") (class "Default")
      (node (ref "PLL3") (pin "8") (pinfunction "OUPUT_8") (pintype "bidirectional"))
      (node (ref "R8") (pin "1") (pinfunction "1_1") (pintype "passive"))
      (node (ref "U1") (pin "28") (pinfunction "PB7_28") (pintype "bidirectional"))
    )
    (net (code "54") (name "PLL_G") (class "Default")
      (node (ref "PLL2") (pin "8") (pinfunction "OUPUT_8") (pintype "bidirectional"))
      (node (ref "R7") (pin "1") (pinfunction "1_1") (pintype "passive"))
      (node (ref "U1") (pin "27") (pinfunction "PB6_27") (pintype "bidirectional"))
    )
    (net (code "55") (name "PLL_R") (class "Default")
      (node (ref "PLL1") (pin "8") (pinfunction "OUPUT_8") (pintype "bidirectional"))
      (node (ref "R6") (pin "1") (pinfunction "1_1") (pintype "passive"))
      (node (ref "U1") (pin "26") (pinfunction "PB5_26") (pintype "bidirectional"))
    )
    (net (code "56") (name "RX_OUT") (class "Default")
      (node (ref "C28") (pin "1") (pinfunction "1_1") (pintype "passive"))
      (node (ref "C32") (pin "1") (pinfunction "1_1") (pintype "passive"))
      (node (ref "C33") (pin "1") (pinfunction "1_1") (pintype "passive"))
      (node (ref "C34") (pin "1") (pinfunction "1_1") (pintype "passive"))
      (node (ref "L1") (pin "2") (pinfunction "2_2") (pintype "passive"))
      (node (ref "R28") (pin "2") (pinfunction "2_2") (pintype "passive"))
      (node (ref "TP9") (pin "TP") (pinfunction "TP_TP") (pintype "input"))
    )
    (net (code "57") (name "STM_SWCLK") (class "Default")
      (node (ref "R21") (pin "2") (pinfunction "2_2") (pintype "passive"))
      (node (ref "U1") (pin "22") (pinfunction "PA14_22") (pintype "bidirectional"))
    )
    (net (code "58") (name "STM_SWDAT") (class "Default")
      (node (ref "R20") (pin "2") (pinfunction "2_2") (pintype "passive"))
      (node (ref "U1") (pin "21") (pinfunction "PA13_21") (pintype "bidirectional"))
    )
    (net (code "59") (name "STM_SWO") (class "Default")
      (node (ref "R19") (pin "2") (pinfunction "2_2") (pintype "passive"))
      (node (ref "U1") (pin "23") (pinfunction "PA15_23") (pintype "bidirectional"))
    )
    (net (code "60") (name "TRIGGER") (class "Default")
      (node (ref "C38") (pin "1") (pinfunction "1_1") (pintype "passive"))
      (node (ref "R30") (pin "1") (pinfunction "1_1") (pintype "passive"))
      (node (ref "SW3") (pin "2") (pinfunction "2_2") (pintype "bidirectional"))
      (node (ref "U1") (pin "10") (pinfunction "PA4_10") (pintype "bidirectional"))
    )
    (net (code "61") (name "TX_OUT") (class "Default")
      (node (ref "HEX1") (pin "10") (pinfunction "5Y_10") (pintype "bidirectional"))
      (node (ref "HEX1") (pin "12") (pinfunction "6Y_12") (pintype "bidirectional"))
      (node (ref "HEX1") (pin "2") (pinfunction "1Y_2") (pintype "bidirectional"))
      (node (ref "HEX1") (pin "4") (pinfunction "2Y_4") (pintype "bidirectional"))
      (node (ref "HEX1") (pin "6") (pinfunction "3Y_6") (pintype "bidirectional"))
      (node (ref "TP_TX_OUT") (pin "TP") (pinfunction "TP_TP") (pintype "input"))
      (node (ref "U2") (pin "5") (pinfunction "NC2_5") (pintype "bidirectional"))
    )
    (net (code "62") (name "TX{slash}RX") (class "Default")
      (node (ref "U1") (pin "8") (pinfunction "PA2_8") (pintype "bidirectional"))
      (node (ref "U2") (pin "1") (pinfunction "CB_1") (pintype "bidirectional"))
    )
    (net (code "63") (name "unconnected-(U1A-PA8-Pad18)") (class "Default")
      (node (ref "U1") (pin "18") (pinfunction "PA8_18") (pintype "bidirectional"))
    )
    (net (code "64") (name "unconnected-(U1A-PF0{slash}OSC_IN-Pad2)") (class "Default")
      (node (ref "U1") (pin "2") (pinfunction "PF0/OSC_IN_2") (pintype "bidirectional"))
    )
    (net (code "65") (name "unconnected-(U1A-PF1{slash}OSC_OUT-Pad3)") (class "Default")
      (node (ref "U1") (pin "3") (pinfunction "PF1/OSC_OUT_3") (pintype "bidirectional"))
    )
  )
)
